# regulator_interposer.net
KiCad netlist of a schematic drawn in Altium Designer
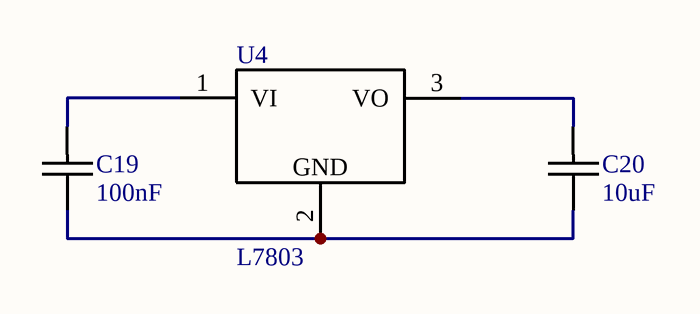
[diagram p0: regulator_interposer.SchDoc]

(export (version "E")
  (design (tool "Eeschema 10.0.6"))
  (components
    (comp (ref "C19")
      (value "100nF")
      (footprint "0603C-GENERIC")
      (description "CAPACITOR 0603 CERAMIC")
      (fields
        (field (name "MANUFACTURER PART NUMBER") "C1608X7R1E104K")
        (field (name "MANUFACTURER") "TDK Corporation")
      )
      (libsource (lib "vh_altium_library") (part "0603C-100NF-25V-X7R-TDK"))
    )
    (comp (ref "C20")
      (value "10uF")
      (footprint "CAPC6032X25N")
      (description "CAPACITOR 2413 TANT")
      (fields
        (field (name "MANUFACTURER PART NUMBER") "T491C106K016AT")
        (field (name "MANUFACTURER") "Kemet")
      )
      (libsource (lib "vh_altium_library") (part "0603C-10UF-10V-X5R-TDK"))
    )
    (comp (ref "U4")
      (value "L7803")
      (footprint "to220-123-v")
      (description "LINEAR REGULATOR 5.0V")
      (libsource (lib "vh_altium_library") (part "L7805-TO220"))
    )
  )
  (nets
    (net (code "1") (name "Net-(C19-Pad2)") (class "Default")
      (node (ref "C19") (pin "2") (pintype "passive"))
      (node (ref "C20") (pin "2") (pintype "passive"))
      (node (ref "U4") (pin "2") (pintype "passive"))
    )
    (net (code "2") (name "Net-(U4-VI)") (class "Default")
      (node (ref "C19") (pin "1") (pintype "passive"))
      (node (ref "U4") (pin "1") (pinfunction "VI_1") (pintype "passive"))
    )
    (net (code "3") (name "Net-(U4-VO)") (class "Default")
      (node (ref "C20") (pin "1") (pintype "passive"))
      (node (ref "U4") (pin "3") (pinfunction "VO_3") (pintype "passive"))
    )
  )
)
